# PMOD_CAN.net
KiCad netlist of a schematic drawn in Altium Designer
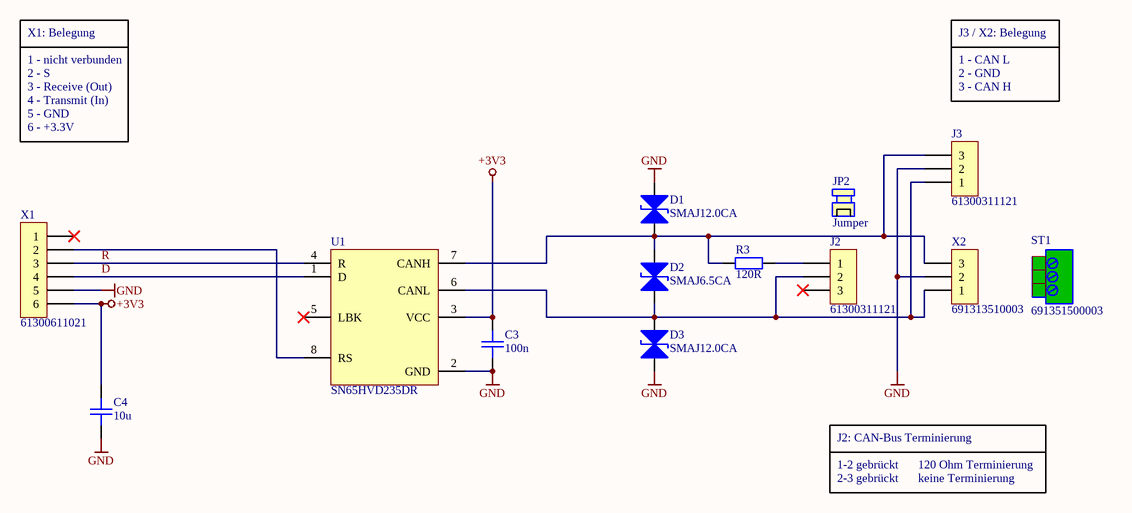
[diagram p0: PMOD_CAN.SchDoc]

(export (version "E")
  (design (tool "Eeschema 10.0.6"))
  (components
    (comp (ref "C3")
      (value "100n")
      (footprint "0805-C")
      (description "CAP CER 0.1UF 50V X8R 0805")
      (fields
        (field (name "MANUFACTURER PARTNO") "GCM21BR91H104KA37L")
        (field (name "MANUFACTURER") "Murata Electronics")
      )
      (libsource (lib "Dual-CAN-HAT") (part "Capacitor 100n 0805"))
    )
    (comp (ref "C4")
      (value "10u")
      (footprint "0805-C")
      (description "CAP CER 10UF 16V X5R 0805")
      (fields
        (field (name "MANUFACTURER PARTNO") "EMK212BBJ106KGHT")
        (field (name "MANUFACTURER") "Taiyo Yuden")
      )
      (libsource (lib "Dual-CAN-HAT") (part "Capacitor 10u 0805"))
    )
    (comp (ref "D1")
      (value "SMAJ12.0CA")
      (footprint "SMA-BIDIRECTIONAL")
      (description "TVS DIODE 12V 19.9V DO214AC")
      (fields
        (field (name "MANUFACTURER PARTNO") "SMAJ12CA-TP")
        (field (name "MANUFACTURER") "Micro Commercial Co")
      )
      (libsource (lib "Dual-CAN-HAT") (part "Diode TVS SMAJ12.0CA"))
    )
    (comp (ref "D2")
      (value "SMAJ6.5CA")
      (footprint "SMA-BIDIRECTIONAL")
      (description "TVS DIODE 6.5V 11.2V DO214AC")
      (fields
        (field (name "MANUFACTURER PARTNO") "SMAJ6.5CA-TP")
        (field (name "MANUFACTURER") "Micro Commercial Co")
      )
      (libsource (lib "Dual-CAN-HAT") (part "Diode TVS SMAJ6.5CA"))
    )
    (comp (ref "D3")
      (value "SMAJ12.0CA")
      (footprint "SMA-BIDIRECTIONAL")
      (description "TVS DIODE 12V 19.9V DO214AC")
      (fields
        (field (name "MANUFACTURER PARTNO") "SMAJ12CA-TP")
        (field (name "MANUFACTURER") "Micro Commercial Co")
      )
      (libsource (lib "Dual-CAN-HAT") (part "Diode TVS SMAJ12.0CA"))
    )
    (comp (ref "J2")
      (value "61300311121")
      (footprint "WE-61300311121")
      (description "CONN HEADER VERT 3POS 2.54MM")
      (fields (field (name "MANUFACTURER") "Würth Elektronik"))
      (libsource (lib "CAN_RS485_BREAKOUT") (part "WE 61300311121"))
    )
    (comp (ref "J3")
      (value "61300311121")
      (footprint "WE-61300311121")
      (description "CONN HEADER VERT 3POS 2.54MM")
      (fields (field (name "MANUFACTURER") "Würth Elektronik"))
      (libsource (lib "") (part "WE 61300311121_1"))
    )
    (comp (ref "JP2")
      (value "Jumper")
      (description "JUMPER W/TEST PNT 1X2PINS 2.54MM")
      (fields
        (field (name "MANUFACTURER") "Würth Elektronik")
        (field (name "MANUFACTURER PARTNO") "60900213421")
      )
      (libsource (lib "Dual-CAN-HAT") (part "Jumper"))
    )
    (comp (ref "R3")
      (value "120R")
      (footprint "1206-R")
      (description "RES SMD 120 OHM 1% 1/4W 1206")
      (fields (field (name "MANUFACTURER") "Yageo") (field (name "MANUFACTURER PARTNO") "RC1206FR-07120RL"))
      (libsource (lib "CAN_RS485_BREAKOUT") (part "Resistor 120R 1206"))
    )
    (comp (ref "ST1")
      (value "691351500003")
      (description "TERM BLOCK PLUG 3POS 5.08MM")
      (fields (field (name "MANUFACTURER") "Würth Elektronik"))
      (libsource (lib "Dual-CAN-HAT") (part "Plug WE 691351500003"))
    )
    (comp (ref "U1")
      (value "SN65HVD235DR")
      (footprint "SOIC-8")
      (description "IC TRANSCEIVER HALF 1/1 8SOIC")
      (fields (field (name "MANUFACTURER") "Texas Instruments"))
      (libsource (lib "PMOD_CAN") (part "SN65HVD235DR SOIC8"))
    )
    (comp (ref "X1")
      (value "61300611021")
      (footprint "WE-61302021121")
      (description "CONN HEADER R/A 6POS 2.54MM")
      (fields (field (name "MANUFACTURER") "Würth Elektronik"))
      (libsource (lib "CAN_RS485_BREAKOUT") (part "PMOD Plug 6X1"))
    )
    (comp (ref "X2")
      (value "691313510003")
      (footprint "WE-691313510003")
      (description "TERM BLOCK HDR 3POS 90DEG 5.08MM")
      (fields (field (name "MANUFACTURER") "Würth Elektronik"))
      (libsource (lib "CAN_RS485_BREAKOUT") (part "WE 691313510003"))
    )
  )
  (nets
    (net (code "1") (name "+3V3") (class "Default")
      (node (ref "C3") (pin "1") (pinfunction "1_1") (pintype "passive"))
      (node (ref "C4") (pin "2") (pinfunction "2_2") (pintype "passive"))
      (node (ref "U1") (pin "3") (pinfunction "VCC_3") (pintype "power_in"))
      (node (ref "X1") (pin "6") (pinfunction "6_6") (pintype "passive"))
    )
    (net (code "2") (name "/D") (class "Default")
      (node (ref "U1") (pin "1") (pinfunction "D_1") (pintype "passive"))
      (node (ref "X1") (pin "4") (pinfunction "4_4") (pintype "passive"))
    )
    (net (code "3") (name "/R") (class "Default")
      (node (ref "U1") (pin "4") (pinfunction "R_4") (pintype "passive"))
      (node (ref "X1") (pin "3") (pinfunction "3_3") (pintype "passive"))
    )
    (net (code "4") (name "GND") (class "Default")
      (node (ref "C3") (pin "2") (pinfunction "2_2") (pintype "passive"))
      (node (ref "C4") (pin "1") (pinfunction "1_1") (pintype "passive"))
      (node (ref "D1") (pin "1") (pinfunction "A1_1") (pintype "passive"))
      (node (ref "D3") (pin "2") (pinfunction "A2_2") (pintype "passive"))
      (node (ref "J3") (pin "2") (pinfunction "2_2") (pintype "passive"))
      (node (ref "U1") (pin "2") (pinfunction "GND_2") (pintype "power_in"))
      (node (ref "X1") (pin "5") (pinfunction "5_5") (pintype "passive"))
      (node (ref "X2") (pin "2") (pinfunction "2_2") (pintype "passive"))
    )
    (net (code "5") (name "Net-(D1-A2)") (class "Default")
      (node (ref "D1") (pin "2") (pinfunction "A2_2") (pintype "passive"))
      (node (ref "D2") (pin "1") (pinfunction "A1_1") (pintype "passive"))
      (node (ref "J3") (pin "3") (pinfunction "3_3") (pintype "passive"))
      (node (ref "R3") (pin "1") (pinfunction "1_1") (pintype "passive"))
      (node (ref "U1") (pin "7") (pinfunction "CANH_7") (pintype "passive"))
      (node (ref "X2") (pin "3") (pinfunction "3_3") (pintype "passive"))
    )
    (net (code "6") (name "Net-(D2-A2)") (class "Default")
      (node (ref "D2") (pin "2") (pinfunction "A2_2") (pintype "passive"))
      (node (ref "D3") (pin "1") (pinfunction "A1_1") (pintype "passive"))
      (node (ref "J2") (pin "2") (pinfunction "2_2") (pintype "passive"))
      (node (ref "J3") (pin "1") (pinfunction "1_1") (pintype "passive"))
      (node (ref "U1") (pin "6") (pinfunction "CANL_6") (pintype "passive"))
      (node (ref "X2") (pin "1") (pinfunction "1_1") (pintype "passive"))
    )
    (net (code "7") (name "Net-(J2-Pad1)") (class "Default")
      (node (ref "J2") (pin "1") (pinfunction "1_1") (pintype "passive"))
      (node (ref "R3") (pin "2") (pinfunction "2_2") (pintype "passive"))
    )
    (net (code "8") (name "Net-(U1-RS)") (class "Default")
      (node (ref "U1") (pin "8") (pinfunction "RS_8") (pintype "passive"))
      (node (ref "X1") (pin "2") (pinfunction "2_2") (pintype "passive"))
    )
    (net (code "9") (name "unconnected-(J2-Pad3)") (class "Default")
      (node (ref "J2") (pin "3") (pinfunction "3_3") (pintype "passive+no_connect"))
    )
    (net (code "10") (name "unconnected-(U1-LBK-Pad5)") (class "Default")
      (node (ref "U1") (pin "5") (pinfunction "LBK_5") (pintype "passive+no_connect"))
    )
    (net (code "11") (name "unconnected-(X1-Pad1)") (class "Default")
      (node (ref "X1") (pin "1") (pinfunction "1_1") (pintype "passive+no_connect"))
    )
  )
)
